# irsensorwafer.net
KiCad netlist of a schematic drawn in EAGLE
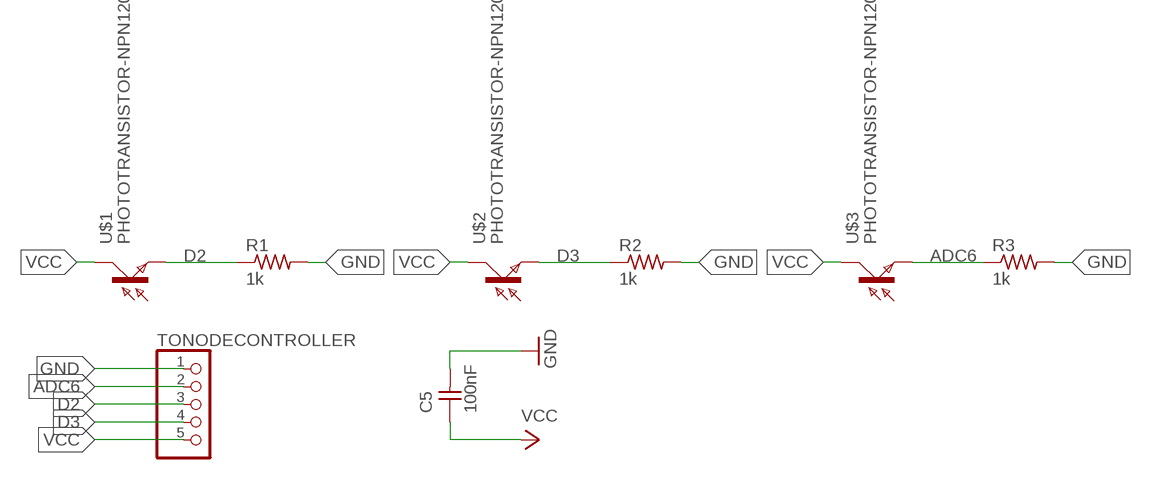
[diagram p0: schematic, sheet 1]

(export (version "E")
  (design (tool "Eeschema 10.0.6"))
  (components
    (comp (ref "C5")
      (value "100nF")
      (footprint "eagle-import:C1206FAB")
      (libsource (lib "eagle-import") (part "CAP-UNPOLARIZEDFAB"))
    )
    (comp (ref "R1")
      (value "1k")
      (footprint "eagle-import:R1206FAB")
      (libsource (lib "eagle-import") (part "RES-US1206FAB"))
    )
    (comp (ref "R2")
      (value "1k")
      (footprint "eagle-import:R1206FAB")
      (libsource (lib "eagle-import") (part "RES-US1206FAB"))
    )
    (comp (ref "R3")
      (value "1k")
      (footprint "eagle-import:R1206FAB")
      (libsource (lib "eagle-import") (part "RES-US1206FAB"))
    )
    (comp (ref "TONODECONTROLLER")
      (value "PINHD-1X5")
      (footprint "eagle-import:1X05")
      (libsource (lib "eagle-import") (part "PINHD-1X5"))
    )
    (comp (ref "U$1")
      (value "PHOTOTRANSISTOR-NPN1206")
      (footprint "eagle-import:OP1206")
      (libsource (lib "eagle-import") (part "PHOTOTRANSISTOR-NPN1206"))
    )
    (comp (ref "U$2")
      (value "PHOTOTRANSISTOR-NPN1206")
      (footprint "eagle-import:OP1206")
      (libsource (lib "eagle-import") (part "PHOTOTRANSISTOR-NPN1206"))
    )
    (comp (ref "U$3")
      (value "PHOTOTRANSISTOR-NPN1206")
      (footprint "eagle-import:OP1206")
      (libsource (lib "eagle-import") (part "PHOTOTRANSISTOR-NPN1206"))
    )
  )
  (nets
    (net (code "1") (name "ADC6") (class "Default")
      (node (ref "R3") (pin "1") (pinfunction "1_1") (pintype "passive"))
      (node (ref "TONODECONTROLLER") (pin "2") (pinfunction "2_2") (pintype "passive"))
      (node (ref "U$3") (pin "EMITTER") (pinfunction "E_EMITTER") (pintype "passive"))
    )
    (net (code "2") (name "D2") (class "Default")
      (node (ref "R1") (pin "1") (pinfunction "1_1") (pintype "passive"))
      (node (ref "TONODECONTROLLER") (pin "3") (pinfunction "3_3") (pintype "passive"))
      (node (ref "U$1") (pin "EMITTER") (pinfunction "E_EMITTER") (pintype "passive"))
    )
    (net (code "3") (name "D3") (class "Default")
      (node (ref "R2") (pin "1") (pinfunction "1_1") (pintype "passive"))
      (node (ref "TONODECONTROLLER") (pin "4") (pinfunction "4_4") (pintype "passive"))
      (node (ref "U$2") (pin "EMITTER") (pinfunction "E_EMITTER") (pintype "passive"))
    )
    (net (code "4") (name "GND") (class "Default")
      (node (ref "C5") (pin "2") (pinfunction "2_2") (pintype "passive"))
      (node (ref "R1") (pin "2") (pinfunction "2_2") (pintype "passive"))
      (node (ref "R2") (pin "2") (pinfunction "2_2") (pintype "passive"))
      (node (ref "R3") (pin "2") (pinfunction "2_2") (pintype "passive"))
      (node (ref "TONODECONTROLLER") (pin "1") (pinfunction "1_1") (pintype "passive"))
    )
    (net (code "5") (name "VCC") (class "Default")
      (node (ref "C5") (pin "1") (pinfunction "1_1") (pintype "passive"))
      (node (ref "TONODECONTROLLER") (pin "5") (pinfunction "5_5") (pintype "passive"))
      (node (ref "U$1") (pin "COLLECTOR") (pinfunction "C_COLLECTOR") (pintype "passive"))
      (node (ref "U$2") (pin "COLLECTOR") (pinfunction "C_COLLECTOR") (pintype "passive"))
      (node (ref "U$3") (pin "COLLECTOR") (pinfunction "C_COLLECTOR") (pintype "passive"))
    )
  )
)
